# Esp8266.net
KiCad netlist of a schematic drawn in Altium Designer
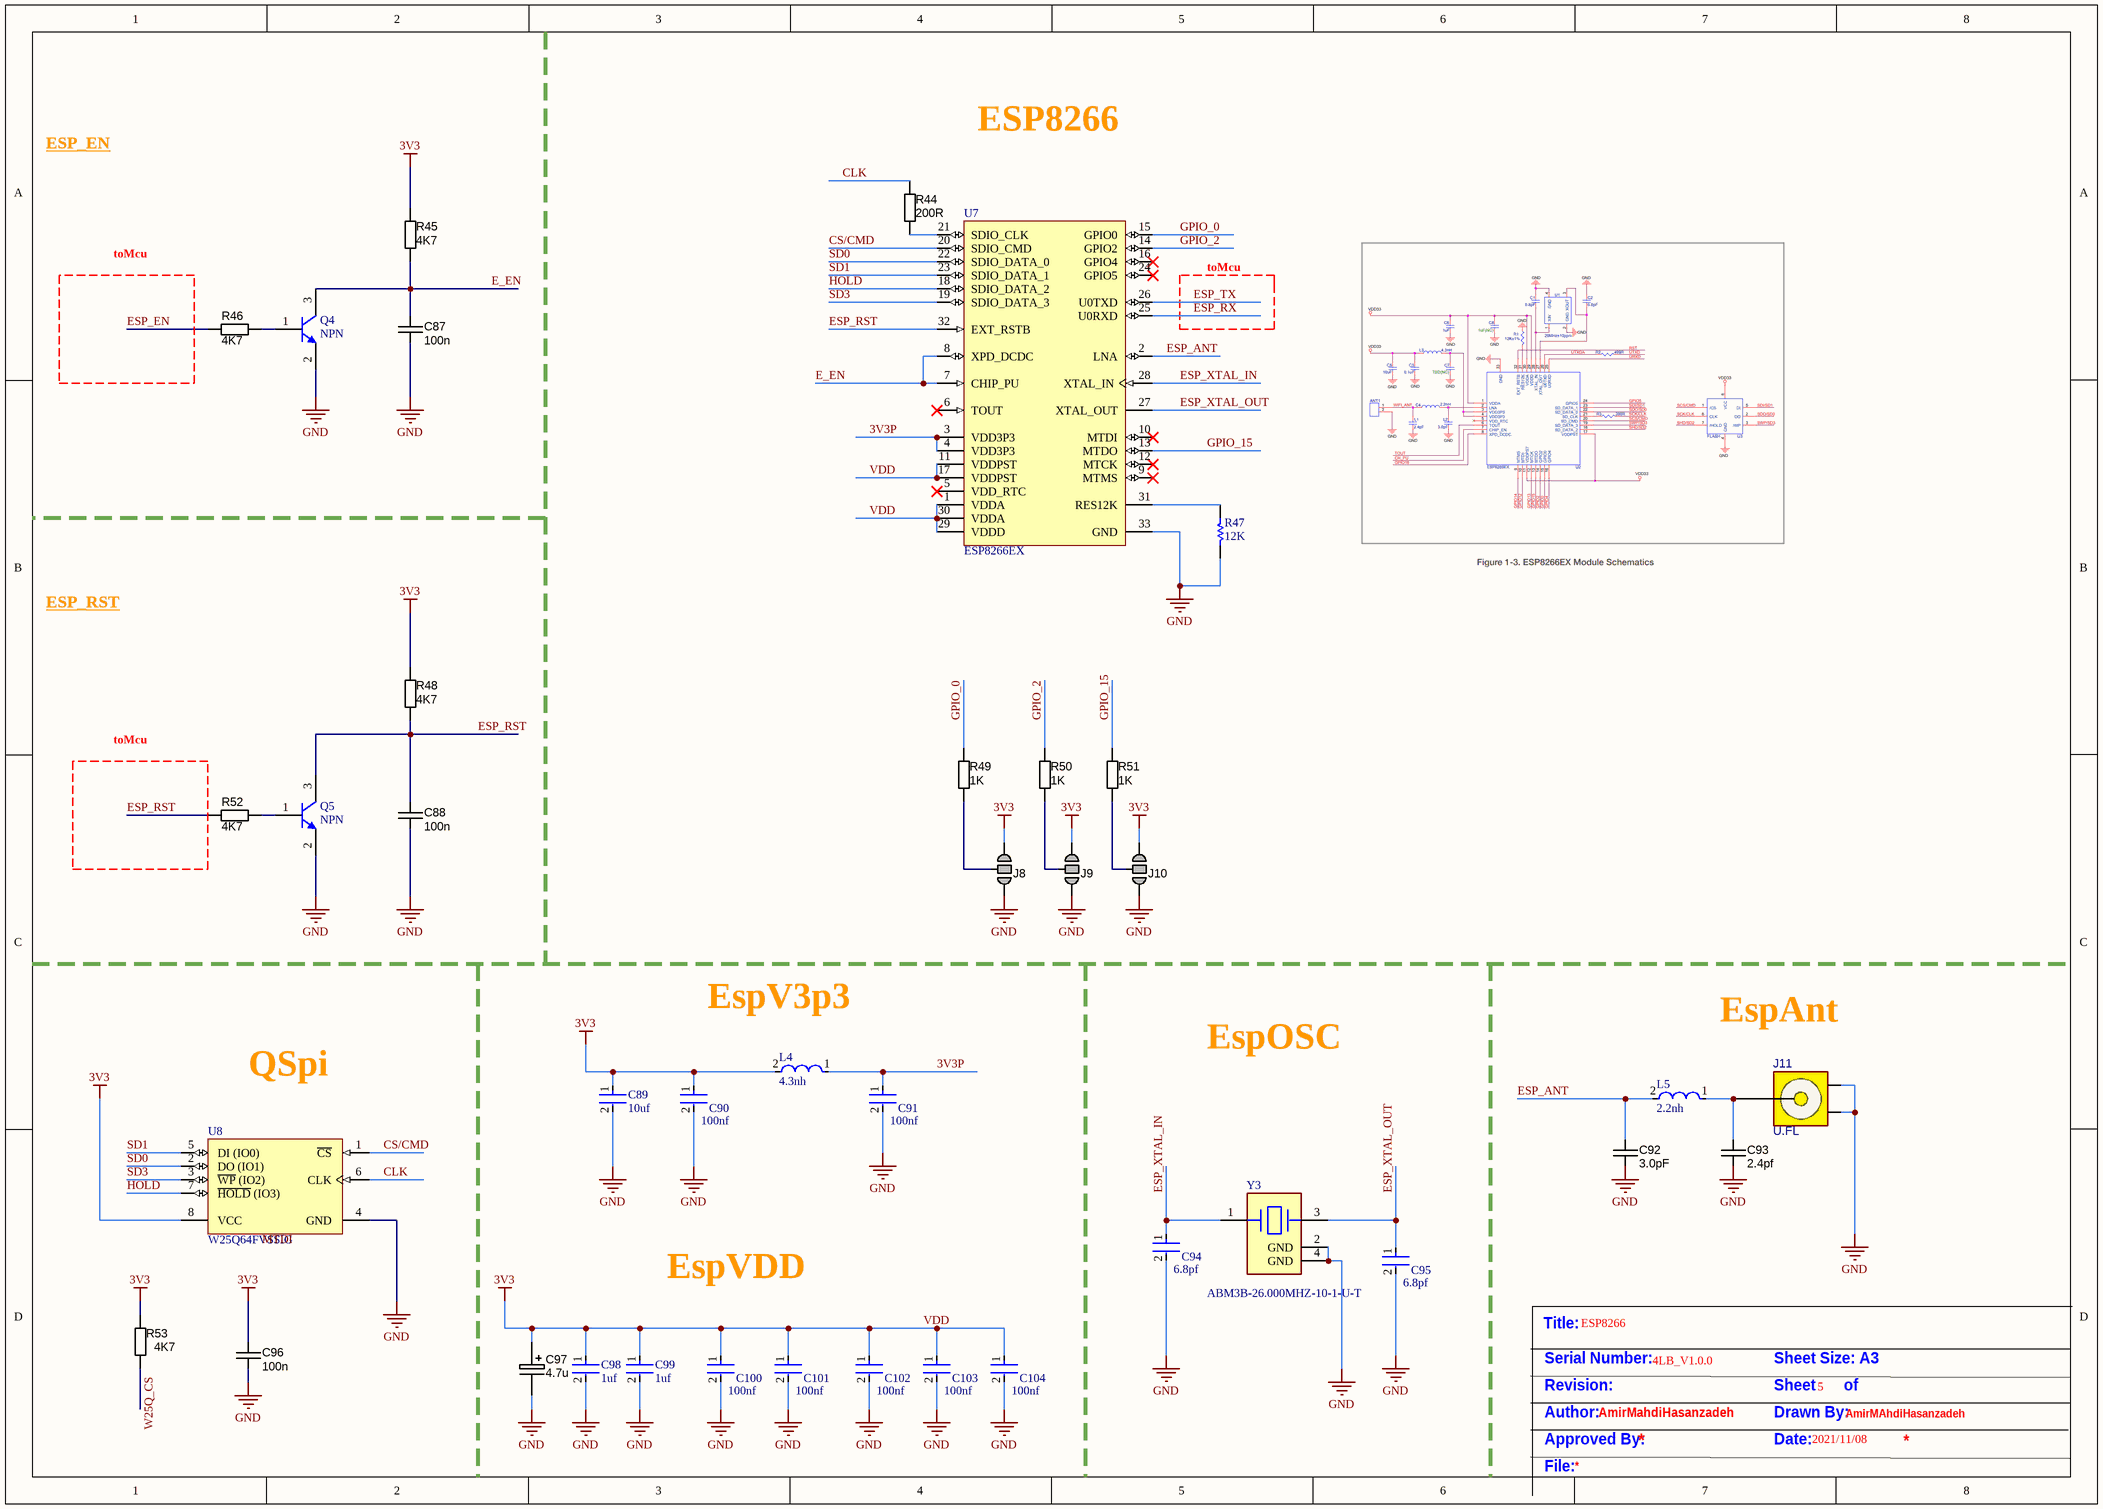
[diagram p0: Esp8266.SchDoc]

(export (version "E")
  (design (tool "Eeschema 10.0.6"))
  (components
    (comp (ref "C87")
      (value "100n")
      (footprint "CAPC1608X90N")
      (description "Capacitor SMD Cer 100nF 10% 50V X7R 0603")
      (fields (field (name "TOLERANCE") "±10%") (field (name "Comment") "approved sub OK"))
      (libsource (lib "PBL - Capacitors") (part "CAPC_100n_0603_X7R_50V_10%"))
    )
    (comp (ref "C88")
      (value "100n")
      (footprint "CAPC1608X90N")
      (description "Capacitor SMD Cer 100nF 10% 50V X7R 0603")
      (fields (field (name "TOLERANCE") "±10%") (field (name "Comment") "approved sub OK"))
      (libsource (lib "PBL - Capacitors") (part "CAPC_100n_0603_X7R_50V_10%"))
    )
    (comp (ref "C89")
      (value "10uf")
      (footprint "FP-GRM31C-0_2-e0_3_0_8-MFG")
      (description "Chip Multilayer Ceramic Capacitors for General Purpose, 1206, 10uF, X7R, 15%, 10%, 10V")
      (fields (field (name "VOLTAGE") "10V") (field (name "TOLERANCE") "10%"))
      (libsource (lib "Altium Content Vault") (part "02cd4be3c70576c341d710602a673aa"))
    )
    (comp (ref "C90")
      (value "100nf")
      (footprint "FP-CGA3E-0_3-0_1-IPC_A")
      (description "Cap Ceramic 100nF 50V X7R 10% Pad SMD 0603 +125°C Automotive T/R")
      (fields (field (name "TOLERANCE") "10%") (field (name "VOLTAGE") "50V"))
      (libsource (lib "Altium Content Vault") (part "b4654b650e69147ec39a6b967a45e02"))
    )
    (comp (ref "C91")
      (value "100nf")
      (footprint "FP-CGA3E-0_3-0_1-IPC_A")
      (description "Cap Ceramic 100nF 50V X7R 10% Pad SMD 0603 +125°C Automotive T/R")
      (fields (field (name "TOLERANCE") "10%") (field (name "VOLTAGE") "50V"))
      (libsource (lib "Altium Content Vault") (part "b4654b650e69147ec39a6b967a45e02"))
    )
    (comp (ref "C92")
      (value "3.0pF")
      (footprint "C0402")
      (description "Capacitor SMD Cer 3.0pF 10% 50V X7R 0603")
      (fields (field (name "TOLERANCE") "±10%"))
      (libsource (lib "PBL - Capacitors") (part "CAPC_100n_0603_X7R_50V_10%"))
    )
    (comp (ref "C93")
      (value "2.4pf")
      (footprint "C0402")
      (description "Capacitor SMD Cer 100nF 10% 50V X7R 0603")
      (fields (field (name "TOLERANCE") "±10%") (field (name "Comment") "approved sub OK"))
      (libsource (lib "PBL - Capacitors") (part "CAPC_100n_0603_X7R_50V_10%"))
    )
    (comp (ref "C94")
      (value "6.8pf")
      (footprint "FP-CGA3E-0_3-0_1-IPC_A")
      (description "Cap Ceramic 100nF 50V X7R 10% Pad SMD 0603 +125°C Automotive T/R")
      (fields (field (name "TOLERANCE") "10%") (field (name "VOLTAGE") "50V"))
      (libsource (lib "Altium Content Vault") (part "b4654b650e69147ec39a6b967a45e02"))
    )
    (comp (ref "C95")
      (value "6.8pf")
      (footprint "FP-CGA3E-0_3-0_1-IPC_A")
      (description "Cap Ceramic 100nF 50V X7R 10% Pad SMD 0603 +125°C Automotive T/R")
      (fields (field (name "TOLERANCE") "10%") (field (name "VOLTAGE") "50V"))
      (libsource (lib "Altium Content Vault") (part "b4654b650e69147ec39a6b967a45e02"))
    )
    (comp (ref "C96")
      (value "100n")
      (footprint "CAPC1608X90N")
      (description "Capacitor SMD Cer 100nF 10% 50V X7R 0603")
      (fields (field (name "TOLERANCE") "±10%") (field (name "Comment") "approved sub OK"))
      (libsource (lib "PBL - Capacitors") (part "CAPC_100n_0603_X7R_50V_10%"))
    )
    (comp (ref "C97")
      (value "4.7u")
      (footprint "C_TN_3528")
      (description "Capacitor SMD Tantalum 10uF 10% 16V 3216-18")
      (fields (field (name "TOLERANCE") "±10%"))
      (libsource (lib "PBL - Capacitors") (part "CAPT_4u7_3216_16V"))
    )
    (comp (ref "C98")
      (value "1uf")
      (footprint "FP-GRM31C-0_2-e0_3_0_8-MFG")
      (description "Chip Multilayer Ceramic Capacitors for General Purpose, 1206, 10uF, X7R, 15%, 10%, 10V")
      (fields (field (name "VOLTAGE") "10V") (field (name "TOLERANCE") "10%"))
      (libsource (lib "Altium Content Vault") (part "02cd4be3c70576c341d710602a673aa"))
    )
    (comp (ref "C99")
      (value "1uf")
      (footprint "FP-GRM31C-0_2-e0_3_0_8-MFG")
      (description "Chip Multilayer Ceramic Capacitors for General Purpose, 1206, 10uF, X7R, 15%, 10%, 10V")
      (fields (field (name "VOLTAGE") "10V") (field (name "TOLERANCE") "10%"))
      (libsource (lib "Altium Content Vault") (part "02cd4be3c70576c341d710602a673aa"))
    )
    (comp (ref "C100")
      (value "100nf")
      (footprint "FP-CGA3E-0_3-0_1-IPC_A")
      (description "Cap Ceramic 100nF 50V X7R 10% Pad SMD 0603 +125°C Automotive T/R")
      (fields (field (name "TOLERANCE") "10%") (field (name "VOLTAGE") "50V"))
      (libsource (lib "Altium Content Vault") (part "b4654b650e69147ec39a6b967a45e02"))
    )
    (comp (ref "C101")
      (value "100nf")
      (footprint "FP-CGA3E-0_3-0_1-IPC_A")
      (description "Cap Ceramic 100nF 50V X7R 10% Pad SMD 0603 +125°C Automotive T/R")
      (fields (field (name "TOLERANCE") "10%") (field (name "VOLTAGE") "50V"))
      (libsource (lib "Altium Content Vault") (part "b4654b650e69147ec39a6b967a45e02"))
    )
    (comp (ref "C102")
      (value "100nf")
      (footprint "FP-CGA3E-0_3-0_1-IPC_A")
      (description "Cap Ceramic 100nF 50V X7R 10% Pad SMD 0603 +125°C Automotive T/R")
      (fields (field (name "TOLERANCE") "10%") (field (name "VOLTAGE") "50V"))
      (libsource (lib "Altium Content Vault") (part "b4654b650e69147ec39a6b967a45e02"))
    )
    (comp (ref "C103")
      (value "100nf")
      (footprint "FP-CGA3E-0_3-0_1-IPC_A")
      (description "Cap Ceramic 100nF 50V X7R 10% Pad SMD 0603 +125°C Automotive T/R")
      (fields (field (name "TOLERANCE") "10%") (field (name "VOLTAGE") "50V"))
      (libsource (lib "Altium Content Vault") (part "b4654b650e69147ec39a6b967a45e02"))
    )
    (comp (ref "C104")
      (value "100nf")
      (footprint "FP-CGA3E-0_3-0_1-IPC_A")
      (description "Cap Ceramic 100nF 50V X7R 10% Pad SMD 0603 +125°C Automotive T/R")
      (fields (field (name "TOLERANCE") "10%") (field (name "VOLTAGE") "50V"))
      (libsource (lib "Altium Content Vault") (part "b4654b650e69147ec39a6b967a45e02"))
    )
    (comp (ref "J8")
      (value "Jumper")
      (footprint "Jump_3Way")
      (description "SMD jumper")
      (libsource (lib "PBL - Pads and Jumpers") (part "JUMP_3WAY"))
    )
    (comp (ref "J9")
      (value "Jumper")
      (footprint "Jump_3Way")
      (description "SMD jumper")
      (libsource (lib "PBL - Pads and Jumpers") (part "JUMP_3WAY"))
    )
    (comp (ref "J10")
      (value "Jumper")
      (footprint "Jump_3Way")
      (description "SMD jumper")
      (libsource (lib "PBL - Pads and Jumpers") (part "JUMP_3WAY"))
    )
    (comp (ref "J11")
      (value "U.FL")
      (footprint "UFL")
      (description "CONN, RF, U.FL, STRAIGHT, Ultra Miniature Coaxial")
      (fields
        (field (name "MANF_P#") "CONUFL001-SMD, U.FL-R-SMT-1(10), 128-0711-201")
        (field (name "MANF") "Linx, Hirose, Cinch")
      )
      (libsource (lib "conn_rf") (part "CONN_RF_UFL"))
    )
    (comp (ref "L4")
      (value "4.3nh")
      (footprint "FP-CBMF1608-MFG")
      (description "SMD Inductors 4.3nH ±20% 0.56A 0.221Ω 0603")
      (fields (field (name "TOLERANCE") "20%"))
      (libsource (lib "Altium Content Vault") (part "725321dda6339637d4d059423bc1c3c"))
    )
    (comp (ref "L5")
      (value "2.2nh")
      (footprint "FP-CBMF1608-MFG")
      (description "SMD Inductors 2.2nH ±20% 0.56A 0.221Ω 0603")
      (fields (field (name "TOLERANCE") "20%"))
      (libsource (lib "Altium Content Vault") (part "725321dda6339637d4d059423bc1c3c"))
    )
    (comp (ref "Q4")
      (value "NPN")
      (footprint "SOT23-3")
      (description "NPN Bipolar Transistor")
      (fields (field (name "PUBLISHER") "Altium Limited"))
      (libsource (lib "Miscellaneous Devices") (part "NPN"))
    )
    (comp (ref "Q5")
      (value "NPN")
      (footprint "SOT23-3")
      (description "NPN Bipolar Transistor")
      (fields (field (name "PUBLISHER") "Altium Limited"))
      (libsource (lib "Miscellaneous Devices") (part "NPN"))
    )
    (comp (ref "R44")
      (value "200R")
      (footprint "RESC1608X55N")
      (description "Resistor SMD chip 4.7k Ohm 0.1W 5% 0603")
      (fields (field (name "TOLERANCE") "±5%") (field (name "Comment") "Thick Film"))
      (libsource (lib "") (part "RES_4K7_0603_5%_3"))
    )
    (comp (ref "R45")
      (value "4K7")
      (footprint "RESC1608X55N")
      (description "Resistor SMD chip 4.7k Ohm 0.1W 5% 0603")
      (fields (field (name "TOLERANCE") "±5%") (field (name "Comment") "Thick Film"))
      (libsource (lib "") (part "RES_4K7_0603_5%_1"))
    )
    (comp (ref "R46")
      (value "4K7")
      (footprint "RESC1608X55N")
      (description "Resistor SMD chip 4.7k Ohm 0.1W 5% 0603")
      (fields (field (name "TOLERANCE") "±5%") (field (name "Comment") "Thick Film"))
      (libsource (lib "") (part "RES_4K7_0603_5%_2"))
    )
    (comp (ref "R47")
      (value "12K")
      (footprint "RESC1608X55X25ML10T15")
      (description "Chip Resistor, 0 Ohm, +/- 5%, 0.1 W, -55 to 155 degC, 0603 (1608 Metric), RoHS, Tape and Reel")
      (fields (field (name "TOLERANCE") "5%") (field (name "MANUFACTURER") "Yageo"))
      (libsource (lib "Altium Content Vault") (part "RES-2"))
    )
    (comp (ref "R48")
      (value "4K7")
      (footprint "RESC1608X55N")
      (description "Resistor SMD chip 4.7k Ohm 0.1W 5% 0603")
      (fields (field (name "TOLERANCE") "±5%") (field (name "Comment") "Thick Film"))
      (libsource (lib "") (part "RES_4K7_0603_5%_1"))
    )
    (comp (ref "R49")
      (value "1K")
      (footprint "RESC1608X55N")
      (description "Resistor SMD chip 1k Ohm 0.1W 5% 0603")
      (fields (field (name "TOLERANCE") "±5%") (field (name "Comment") "Thick Film"))
      (libsource (lib "") (part "RES_4K7_0603_5%_1"))
    )
    (comp (ref "R50")
      (value "1K")
      (footprint "RESC1608X55N")
      (description "Resistor SMD chip 1k Ohm 0.1W 5% 0603")
      (fields (field (name "TOLERANCE") "±5%") (field (name "Comment") "Thick Film"))
      (libsource (lib "") (part "RES_4K7_0603_5%_1"))
    )
    (comp (ref "R51")
      (value "1K")
      (footprint "RESC1608X55N")
      (description "Resistor SMD chip 1k Ohm 0.1W 5% 0603")
      (fields (field (name "TOLERANCE") "±5%") (field (name "Comment") "Thick Film"))
      (libsource (lib "") (part "RES_4K7_0603_5%_1"))
    )
    (comp (ref "R52")
      (value "4K7")
      (footprint "RESC1608X55N")
      (description "Resistor SMD chip 4.7k Ohm 0.1W 5% 0603")
      (fields (field (name "TOLERANCE") "±5%") (field (name "Comment") "Thick Film"))
      (libsource (lib "") (part "RES_4K7_0603_5%_2"))
    )
    (comp (ref "R53")
      (value "4K7")
      (footprint "RESC1608X55N")
      (description "Resistor SMD chip 4.7k Ohm 0.1W 5% 0603")
      (fields (field (name "TOLERANCE") "±5%") (field (name "Comment") "Thick Film"))
      (libsource (lib "PBL - Resistors") (part "RES_4K7_0603_5%"))
    )
    (comp (ref "U7")
      (value "ESP8266EX")
      (footprint "ESFS-QFN-32_L")
      (description "Low-Power, Highly-Integrated Wi-Fi Solution, 2.5 to 3.6 V, 80 mA, -40 to 125 degC, 32-Pin QFN")
      (fields (field (name "MANUFACTURER") "Espressif Systems"))
      (libsource (lib "Altium Content Vault") (part "ESFS-ESP8266EX-32"))
    )
    (comp (ref "U8")
      (value "W25Q64FVSSIG")
      (footprint "WINB-SOIC-8_M")
      (fields (field (name "MANUFACTURER") "Winbond"))
      (libsource (lib "Altium Content Vault") (part "WINB-W25Q64FVSSIG-SOIC-8"))
    )
    (comp (ref "Y3")
      (value "ABM3B-26.000MHZ-10-1-U-T")
      (footprint "FP-ABM3B-MFG")
      (description "CRYSTAL 26.0000MHZ 10PF SMD")
      (fields (field (name "TOLERANCE") "10ppm") (field (name "MANUFACTURER") "Abracon"))
      (libsource (lib "Altium Content Vault") (part "12c405fa944625e9f113818bc534409"))
    )
  )
  (nets
    (net (code "1") (name "/3V3P") (class "Default")
      (node (ref "C91") (pin "1") (pinfunction "1_1") (pintype "passive"))
      (node (ref "L4") (pin "1") (pinfunction "1_1") (pintype "passive"))
      (node (ref "U7") (pin "3") (pinfunction "VDD3P3_3") (pintype "power_in"))
      (node (ref "U7") (pin "4") (pinfunction "VDD3P3_4") (pintype "power_in"))
    )
    (net (code "2") (name "/CLK") (class "Default")
      (node (ref "R44") (pin "2") (pinfunction "2_2") (pintype "passive"))
      (node (ref "U8") (pin "6") (pinfunction "CLK_6") (pintype "input"))
    )
    (net (code "3") (name "/CS{slash}CMD") (class "Default")
      (node (ref "U7") (pin "20") (pinfunction "SDIO_CMD_20") (pintype "bidirectional"))
      (node (ref "U8") (pin "1") (pinfunction "~{CS}_1") (pintype "input"))
    )
    (net (code "4") (name "/ESP_ANT") (class "Default")
      (node (ref "C92") (pin "1") (pintype "passive"))
      (node (ref "L5") (pin "2") (pinfunction "2_2") (pintype "passive"))
      (node (ref "U7") (pin "2") (pinfunction "LNA_2") (pintype "bidirectional"))
    )
    (net (code "5") (name "/ESP_EN") (class "Default")
      (node (ref "R46") (pin "1") (pinfunction "1_1") (pintype "passive"))
    )
    (net (code "6") (name "/ESP_RST") (class "Default")
      (node (ref "C88") (pin "1") (pintype "passive"))
      (node (ref "Q5") (pin "3") (pinfunction "C_3") (pintype "passive"))
      (node (ref "R48") (pin "2") (pinfunction "2_2") (pintype "passive"))
      (node (ref "R52") (pin "1") (pinfunction "1_1") (pintype "passive"))
      (node (ref "U7") (pin "32") (pinfunction "EXT_RSTB_32") (pintype "input"))
    )
    (net (code "7") (name "/ESP_RX") (class "Default")
      (node (ref "U7") (pin "25") (pinfunction "U0RXD_25") (pintype "bidirectional"))
    )
    (net (code "8") (name "/ESP_TX") (class "Default")
      (node (ref "U7") (pin "26") (pinfunction "U0TXD_26") (pintype "bidirectional"))
    )
    (net (code "9") (name "/ESP_XTAL_IN") (class "Default")
      (node (ref "C94") (pin "1") (pinfunction "1_1") (pintype "passive"))
      (node (ref "U7") (pin "28") (pinfunction "XTAL_IN_28") (pintype "input"))
      (node (ref "Y3") (pin "1") (pinfunction "1_1") (pintype "passive"))
    )
    (net (code "10") (name "/ESP_XTAL_OUT") (class "Default")
      (node (ref "C95") (pin "1") (pinfunction "1_1") (pintype "passive"))
      (node (ref "U7") (pin "27") (pinfunction "XTAL_OUT_27") (pintype "passive"))
      (node (ref "Y3") (pin "3") (pinfunction "3_3") (pintype "passive"))
    )
    (net (code "11") (name "/E_EN") (class "Default")
      (node (ref "C87") (pin "1") (pintype "passive"))
      (node (ref "Q4") (pin "3") (pinfunction "C_3") (pintype "passive"))
      (node (ref "R45") (pin "2") (pinfunction "2_2") (pintype "passive"))
      (node (ref "U7") (pin "7") (pinfunction "CHIP_PU_7") (pintype "input"))
      (node (ref "U7") (pin "8") (pinfunction "XPD_DCDC_8") (pintype "bidirectional"))
    )
    (net (code "12") (name "/GPIO_0") (class "Default")
      (node (ref "R49") (pin "1") (pinfunction "1_1") (pintype "passive"))
      (node (ref "U7") (pin "15") (pinfunction "GPIO0_15") (pintype "bidirectional"))
    )
    (net (code "13") (name "/GPIO_2") (class "Default")
      (node (ref "R50") (pin "1") (pinfunction "1_1") (pintype "passive"))
      (node (ref "U7") (pin "14") (pinfunction "GPIO2_14") (pintype "bidirectional"))
    )
    (net (code "14") (name "/GPIO_15") (class "Default")
      (node (ref "R51") (pin "1") (pinfunction "1_1") (pintype "passive"))
      (node (ref "U7") (pin "13") (pinfunction "MTDO_13") (pintype "bidirectional"))
    )
    (net (code "15") (name "/HOLD") (class "Default")
      (node (ref "U7") (pin "18") (pinfunction "SDIO_DATA_2_18") (pintype "bidirectional"))
      (node (ref "U8") (pin "7") (pinfunction "~{HOLD}_(IO3)_7") (pintype "bidirectional"))
    )
    (net (code "17") (name "/SD0") (class "Default")
      (node (ref "U7") (pin "22") (pinfunction "SDIO_DATA_0_22") (pintype "bidirectional"))
      (node (ref "U8") (pin "2") (pinfunction "DO_(IO1)_2") (pintype "bidirectional"))
    )
    (net (code "18") (name "/SD1") (class "Default")
      (node (ref "U7") (pin "23") (pinfunction "SDIO_DATA_1_23") (pintype "bidirectional"))
      (node (ref "U8") (pin "5") (pinfunction "DI_(IO0)_5") (pintype "bidirectional"))
    )
    (net (code "19") (name "/SD3") (class "Default")
      (node (ref "U7") (pin "19") (pinfunction "SDIO_DATA_3_19") (pintype "bidirectional"))
      (node (ref "U8") (pin "3") (pinfunction "~{WP}_(IO2)_3") (pintype "bidirectional"))
    )
    (net (code "20") (name "/W25Q_CS") (class "Default")
      (node (ref "R53") (pin "2") (pinfunction "2_2") (pintype "passive"))
    )
    (net (code "21") (name "3V3") (class "Default")
      (node (ref "C100") (pin "1") (pinfunction "1_1") (pintype "passive"))
      (node (ref "C101") (pin "1") (pinfunction "1_1") (pintype "passive"))
      (node (ref "C102") (pin "1") (pinfunction "1_1") (pintype "passive"))
      (node (ref "C103") (pin "1") (pinfunction "1_1") (pintype "passive"))
      (node (ref "C104") (pin "1") (pinfunction "1_1") (pintype "passive"))
      (node (ref "C89") (pin "1") (pinfunction "1_1") (pintype "passive"))
      (node (ref "C90") (pin "1") (pinfunction "1_1") (pintype "passive"))
      (node (ref "C96") (pin "1") (pintype "passive"))
      (node (ref "C97") (pin "1") (pintype "passive"))
      (node (ref "C98") (pin "1") (pinfunction "1_1") (pintype "passive"))
      (node (ref "C99") (pin "1") (pinfunction "1_1") (pintype "passive"))
      (node (ref "J10") (pin "3") (pinfunction "3_3") (pintype "passive"))
      (node (ref "J8") (pin "3") (pinfunction "3_3") (pintype "passive"))
      (node (ref "J9") (pin "3") (pinfunction "3_3") (pintype "passive"))
      (node (ref "L4") (pin "2") (pinfunction "2_2") (pintype "passive"))
      (node (ref "R45") (pin "1") (pinfunction "1_1") (pintype "passive"))
      (node (ref "R48") (pin "1") (pinfunction "1_1") (pintype "passive"))
      (node (ref "R53") (pin "1") (pinfunction "1_1") (pintype "passive"))
      (node (ref "U7") (pin "1") (pinfunction "VDDA_1") (pintype "power_in"))
      (node (ref "U7") (pin "11") (pinfunction "VDDPST_11") (pintype "power_in"))
      (node (ref "U7") (pin "17") (pinfunction "VDDPST_17") (pintype "power_in"))
      (node (ref "U7") (pin "29") (pinfunction "VDDD_29") (pintype "power_in"))
      (node (ref "U7") (pin "30") (pinfunction "VDDA_30") (pintype "power_in"))
      (node (ref "U8") (pin "8") (pinfunction "VCC_8") (pintype "power_in"))
    )
    (net (code "22") (name "GND") (class "Default")
      (node (ref "C100") (pin "2") (pinfunction "2_2") (pintype "passive"))
      (node (ref "C101") (pin "2") (pinfunction "2_2") (pintype "passive"))
      (node (ref "C102") (pin "2") (pinfunction "2_2") (pintype "passive"))
      (node (ref "C103") (pin "2") (pinfunction "2_2") (pintype "passive"))
      (node (ref "C104") (pin "2") (pinfunction "2_2") (pintype "passive"))
      (node (ref "C87") (pin "2") (pintype "passive"))
      (node (ref "C88") (pin "2") (pintype "passive"))
      (node (ref "C89") (pin "2") (pinfunction "2_2") (pintype "passive"))
      (node (ref "C90") (pin "2") (pinfunction "2_2") (pintype "passive"))
      (node (ref "C91") (pin "2") (pinfunction "2_2") (pintype "passive"))
      (node (ref "C92") (pin "2") (pintype "passive"))
      (node (ref "C93") (pin "2") (pintype "passive"))
      (node (ref "C94") (pin "2") (pinfunction "2_2") (pintype "passive"))
      (node (ref "C95") (pin "2") (pinfunction "2_2") (pintype "passive"))
      (node (ref "C96") (pin "2") (pintype "passive"))
      (node (ref "C97") (pin "2") (pintype "passive"))
      (node (ref "C98") (pin "2") (pinfunction "2_2") (pintype "passive"))
      (node (ref "C99") (pin "2") (pinfunction "2_2") (pintype "passive"))
      (node (ref "J10") (pin "1") (pinfunction "1_1") (pintype "passive"))
      (node (ref "J11") (pin "2") (pinfunction "G1_2") (pintype "passive"))
      (node (ref "J11") (pin "3") (pinfunction "G2_3") (pintype "passive"))
      (node (ref "J8") (pin "1") (pinfunction "1_1") (pintype "passive"))
      (node (ref "J9") (pin "1") (pinfunction "1_1") (pintype "passive"))
      (node (ref "Q4") (pin "2") (pinfunction "E_2") (pintype "passive"))
      (node (ref "Q5") (pin "2") (pinfunction "E_2") (pintype "passive"))
      (node (ref "R47") (pin "1") (pinfunction "1_1") (pintype "passive"))
      (node (ref "U7") (pin "33") (pinfunction "GND_33") (pintype "power_in"))
      (node (ref "U8") (pin "4") (pinfunction "GND_4") (pintype "power_in"))
      (node (ref "Y3") (pin "2") (pinfunction "GND_2") (pintype "power_in"))
      (node (ref "Y3") (pin "4") (pinfunction "GND_4") (pintype "power_in"))
    )
    (net (code "23") (name "Net-(J8-Pad2)") (class "Default")
      (node (ref "J8") (pin "2") (pinfunction "2_2") (pintype "passive"))
      (node (ref "R49") (pin "2") (pinfunction "2_2") (pintype "passive"))
    )
    (net (code "24") (name "Net-(J9-Pad2)") (class "Default")
      (node (ref "J9") (pin "2") (pinfunction "2_2") (pintype "passive"))
      (node (ref "R50") (pin "2") (pinfunction "2_2") (pintype "passive"))
    )
    (net (code "25") (name "Net-(J10-Pad2)") (class "Default")
      (node (ref "J10") (pin "2") (pinfunction "2_2") (pintype "passive"))
      (node (ref "R51") (pin "2") (pinfunction "2_2") (pintype "passive"))
    )
    (net (code "26") (name "Net-(J11-SIG)") (class "Default")
      (node (ref "C93") (pin "1") (pintype "passive"))
      (node (ref "J11") (pin "1") (pinfunction "SIG_1") (pintype "passive"))
      (node (ref "L5") (pin "1") (pinfunction "1_1") (pintype "passive"))
    )
    (net (code "27") (name "Net-(Q4-B)") (class "Default")
      (node (ref "Q4") (pin "1") (pinfunction "B_1") (pintype "passive"))
      (node (ref "R46") (pin "2") (pinfunction "2_2") (pintype "passive"))
    )
    (net (code "28") (name "Net-(Q5-B)") (class "Default")
      (node (ref "Q5") (pin "1") (pinfunction "B_1") (pintype "passive"))
      (node (ref "R52") (pin "2") (pinfunction "2_2") (pintype "passive"))
    )
    (net (code "29") (name "Net-(U7-RES12K)") (class "Default")
      (node (ref "R47") (pin "2") (pinfunction "2_2") (pintype "passive"))
      (node (ref "U7") (pin "31") (pinfunction "RES12K_31") (pintype "passive"))
    )
    (net (code "30") (name "Net-(U7-SDIO_CLK)") (class "Default")
      (node (ref "R44") (pin "1") (pinfunction "1_1") (pintype "passive"))
      (node (ref "U7") (pin "21") (pinfunction "SDIO_CLK_21") (pintype "bidirectional"))
    )
    (net (code "31") (name "unconnected-(U7-GPIO4-Pad16)") (class "Default")
      (node (ref "U7") (pin "16") (pinfunction "GPIO4_16") (pintype "bidirectional+no_connect"))
    )
    (net (code "32") (name "unconnected-(U7-GPIO5-Pad24)") (class "Default")
      (node (ref "U7") (pin "24") (pinfunction "GPIO5_24") (pintype "bidirectional+no_connect"))
    )
    (net (code "33") (name "unconnected-(U7-MTCK-Pad12)") (class "Default")
      (node (ref "U7") (pin "12") (pinfunction "MTCK_12") (pintype "bidirectional+no_connect"))
    )
    (net (code "34") (name "unconnected-(U7-MTDI-Pad10)") (class "Default")
      (node (ref "U7") (pin "10") (pinfunction "MTDI_10") (pintype "bidirectional+no_connect"))
    )
    (net (code "35") (name "unconnected-(U7-MTMS-Pad9)") (class "Default")
      (node (ref "U7") (pin "9") (pinfunction "MTMS_9") (pintype "bidirectional+no_connect"))
    )
    (net (code "36") (name "unconnected-(U7-TOUT-Pad6)") (class "Default")
      (node (ref "U7") (pin "6") (pinfunction "TOUT_6") (pintype "input+no_connect"))
    )
    (net (code "37") (name "unconnected-(U7-VDD_RTC-Pad5)") (class "Default")
      (node (ref "U7") (pin "5") (pinfunction "VDD_RTC_5") (pintype "power_in+no_connect"))
    )
  )
)
